# Sharp96Lcd.net
KiCad netlist of a schematic drawn in Altium Designer
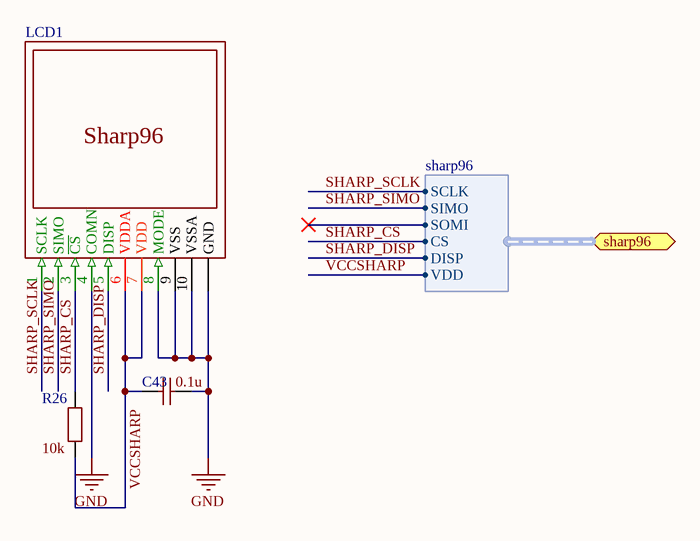
[diagram p0: Sharp96Lcd.SchDoc]

(export (version "E")
  (design (tool "Eeschema 10.0.6"))
  (components
    (comp (ref "C43")
      (value "0.1u")
      (footprint "C0402_h")
      (description "Capacitor")
      (fields (field (name "PUBLISHER") "Altium Limited"))
      (libsource (lib "电子元件封装库") (part "贴片电容-无极性"))
    )
    (comp (ref "LCD1")
      (value "sharp96")
      (footprint "Sharp96")
      (description "sharp96 lcd, 96x96")
      (libsource (lib "电子元件封装库") (part "LCD_Sharp96"))
    )
    (comp (ref "R26")
      (value "10k")
      (footprint "R0402")
      (description "Register")
      (libsource (lib "电子元件封装库") (part "贴片电阻"))
    )
  )
  (nets
    (net (code "2") (name "/SHARP_CS") (class "Default")
      (node (ref "LCD1") (pin "3") (pinfunction "~{CS}_3") (pintype "input"))
      (node (ref "R26") (pin "2") (pinfunction "2_2") (pintype "passive"))
    )
    (net (code "3") (name "/SHARP_DISP") (class "Default")
      (node (ref "LCD1") (pin "5") (pinfunction "DISP_5") (pintype "input"))
    )
    (net (code "4") (name "/SHARP_SCLK") (class "Default")
      (node (ref "LCD1") (pin "1") (pinfunction "SCLK_1") (pintype "input"))
    )
    (net (code "5") (name "/SHARP_SIMO") (class "Default")
      (node (ref "LCD1") (pin "2") (pinfunction "SIMO_2") (pintype "input"))
    )
    (net (code "6") (name "/VCCSHARP") (class "Default")
      (node (ref "C43") (pin "1") (pinfunction "1_1") (pintype "passive"))
      (node (ref "LCD1") (pin "6") (pinfunction "VDDA_6") (pintype "power_in"))
      (node (ref "LCD1") (pin "7") (pinfunction "VDD_7") (pintype "power_in"))
      (node (ref "R26") (pin "1") (pinfunction "1_1") (pintype "passive"))
    )
    (net (code "8") (name "GND") (class "Default")
      (node (ref "C43") (pin "2") (pinfunction "2_2") (pintype "passive"))
      (node (ref "LCD1") (pin "0") (pinfunction "GND_0") (pintype "power_in"))
      (node (ref "LCD1") (pin "10") (pinfunction "VSSA_10") (pintype "power_in"))
      (node (ref "LCD1") (pin "4") (pinfunction "COMN_4") (pintype "input"))
      (node (ref "LCD1") (pin "8") (pinfunction "MODE_8") (pintype "input"))
      (node (ref "LCD1") (pin "9") (pinfunction "VSS_9") (pintype "power_in"))
    )
  )
)
